# Sensors.net
KiCad netlist of a schematic drawn in Altium Designer
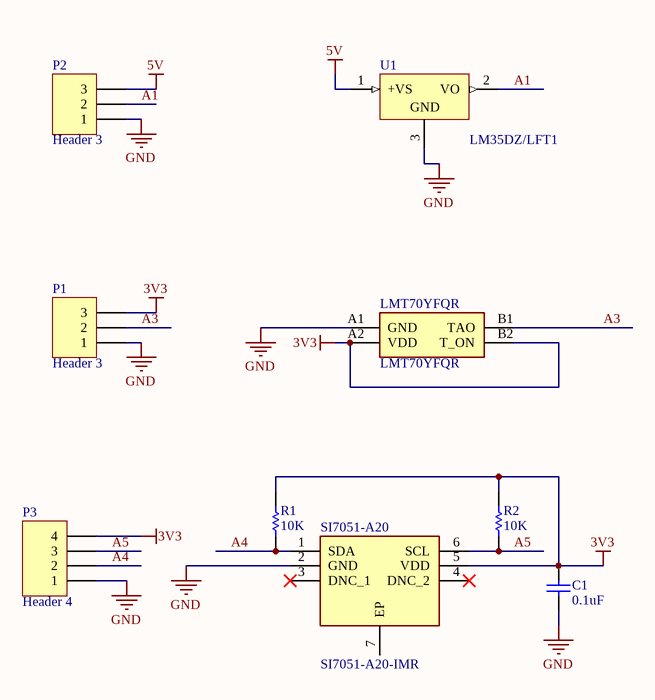
[diagram p0: Sensors.SchDoc]

(export (version "E")
  (design (tool "Eeschema 10.0.6"))
  (components
    (comp (ref "C1") (value "0.1uF") (footprint "C0603_L") (libsource (lib "General") (part "C_SMD")))
    (comp (ref "LMT70YFQR")
      (value "LMT70YFQR")
      (footprint "SamacSys:BGA4C40P2X2_88X88X68")
      (description "Integrated Circuit")
      (fields (field (name "MOUSER PART NUMBER") "595-LMT70YFQR"))
      (libsource (lib "*") (part "LMT70YFQR"))
    )
    (comp (ref "P1")
      (value "Header 3")
      (footprint "HDR1X3")
      (description "Header, 3-Pin")
      (fields (field (name "PUBLISHER") "Altium Limited"))
      (libsource (lib "Miscellaneous Connectors") (part "Header 3"))
    )
    (comp (ref "P2")
      (value "Header 3")
      (footprint "HDR1X3")
      (description "Header, 3-Pin")
      (fields (field (name "PUBLISHER") "Altium Limited"))
      (libsource (lib "Miscellaneous Connectors") (part "Header 3"))
    )
    (comp (ref "P3")
      (value "Header 4")
      (footprint "HDR1X4")
      (description "Header, 4-Pin")
      (fields (field (name "PUBLISHER") "Altium Limited"))
      (libsource (lib "Miscellaneous Connectors") (part "Header 4"))
    )
    (comp (ref "R1") (value "10K") (footprint "R0603_L") (libsource (lib "General") (part "R_SMD")))
    (comp (ref "R2") (value "10K") (footprint "R0603_L") (libsource (lib "General") (part "R_SMD")))
    (comp (ref "SI7051-A20")
      (value "SI7051-A20-IMR")
      (footprint "SamacSys:SON100P300X300X80-7N-D")
      (description "Integrated Circuit")
      (fields (field (name "MOUSER PART NUMBER") "634-SI7051-A20-IMR"))
      (libsource (lib "*") (part "SI7051-A20-IMR"))
    )
    (comp (ref "U1")
      (value "LM35DZ/LFT1")
      (footprint "Z03A")
      (description "IC SENSOR PREC CENT TEMP TO92-3")
      (fields (field (name "MANUFACTURER") "Texas Instruments"))
      (libsource (lib "General") (part "LM35DZ/LFT1"))
    )
  )
  (nets
    (net (code "1") (name "/A1") (class "Default")
      (node (ref "P2") (pin "2") (pinfunction "2_2") (pintype "passive"))
      (node (ref "U1") (pin "2") (pinfunction "VO_2") (pintype "output"))
    )
    (net (code "2") (name "/A3") (class "Default")
      (node (ref "LMT70YFQR") (pin "B1") (pinfunction "TAO_B1") (pintype "passive"))
      (node (ref "P1") (pin "2") (pinfunction "2_2") (pintype "passive"))
    )
    (net (code "3") (name "/A4") (class "Default")
      (node (ref "P3") (pin "2") (pinfunction "2_2") (pintype "passive"))
      (node (ref "R1") (pin "1") (pinfunction "1_1") (pintype "passive"))
      (node (ref "SI7051-A20") (pin "1") (pinfunction "SDA_1") (pintype "passive"))
    )
    (net (code "4") (name "/A5") (class "Default")
      (node (ref "P3") (pin "3") (pinfunction "3_3") (pintype "passive"))
      (node (ref "R2") (pin "1") (pinfunction "1_1") (pintype "passive"))
      (node (ref "SI7051-A20") (pin "6") (pinfunction "SCL_6") (pintype "passive"))
    )
    (net (code "5") (name "3V3") (class "Default")
      (node (ref "C1") (pin "2") (pinfunction "2_2") (pintype "passive"))
      (node (ref "LMT70YFQR") (pin "A2") (pinfunction "VDD_A2") (pintype "passive"))
      (node (ref "LMT70YFQR") (pin "B2") (pinfunction "T_ON_B2") (pintype "passive"))
      (node (ref "P1") (pin "3") (pinfunction "3_3") (pintype "passive"))
      (node (ref "P3") (pin "4") (pinfunction "4_4") (pintype "passive"))
      (node (ref "R1") (pin "2") (pinfunction "2_2") (pintype "passive"))
      (node (ref "R2") (pin "2") (pinfunction "2_2") (pintype "passive"))
      (node (ref "SI7051-A20") (pin "5") (pinfunction "VDD_5") (pintype "passive"))
    )
    (net (code "6") (name "5V") (class "Default")
      (node (ref "P2") (pin "3") (pinfunction "3_3") (pintype "passive"))
      (node (ref "U1") (pin "1") (pinfunction "+VS_1") (pintype "input"))
    )
    (net (code "7") (name "GND") (class "Default")
      (node (ref "C1") (pin "1") (pinfunction "1_1") (pintype "passive"))
      (node (ref "LMT70YFQR") (pin "A1") (pinfunction "GND_A1") (pintype "passive"))
      (node (ref "P1") (pin "1") (pinfunction "1_1") (pintype "passive"))
      (node (ref "P2") (pin "1") (pinfunction "1_1") (pintype "passive"))
      (node (ref "P3") (pin "1") (pinfunction "1_1") (pintype "passive"))
      (node (ref "SI7051-A20") (pin "2") (pinfunction "GND_2") (pintype "passive"))
      (node (ref "U1") (pin "3") (pinfunction "GND_3") (pintype "power_in"))
    )
    (net (code "8") (name "unconnected-(SI7051-A20-DNC_1-Pad3)") (class "Default")
      (node (ref "SI7051-A20") (pin "3") (pinfunction "DNC_1_3") (pintype "passive+no_connect"))
    )
    (net (code "9") (name "unconnected-(SI7051-A20-DNC_2-Pad4)") (class "Default")
      (node (ref "SI7051-A20") (pin "4") (pinfunction "DNC_2_4") (pintype "passive+no_connect"))
    )
    (net (code "10") (name "unconnected-(SI7051-A20-EP-Pad7)") (class "Default")
      (node (ref "SI7051-A20") (pin "7") (pinfunction "EP_7") (pintype "passive"))
    )
  )
)
